# 05_LMS7002M_Misc.net
KiCad netlist of a schematic drawn in Altium Designer
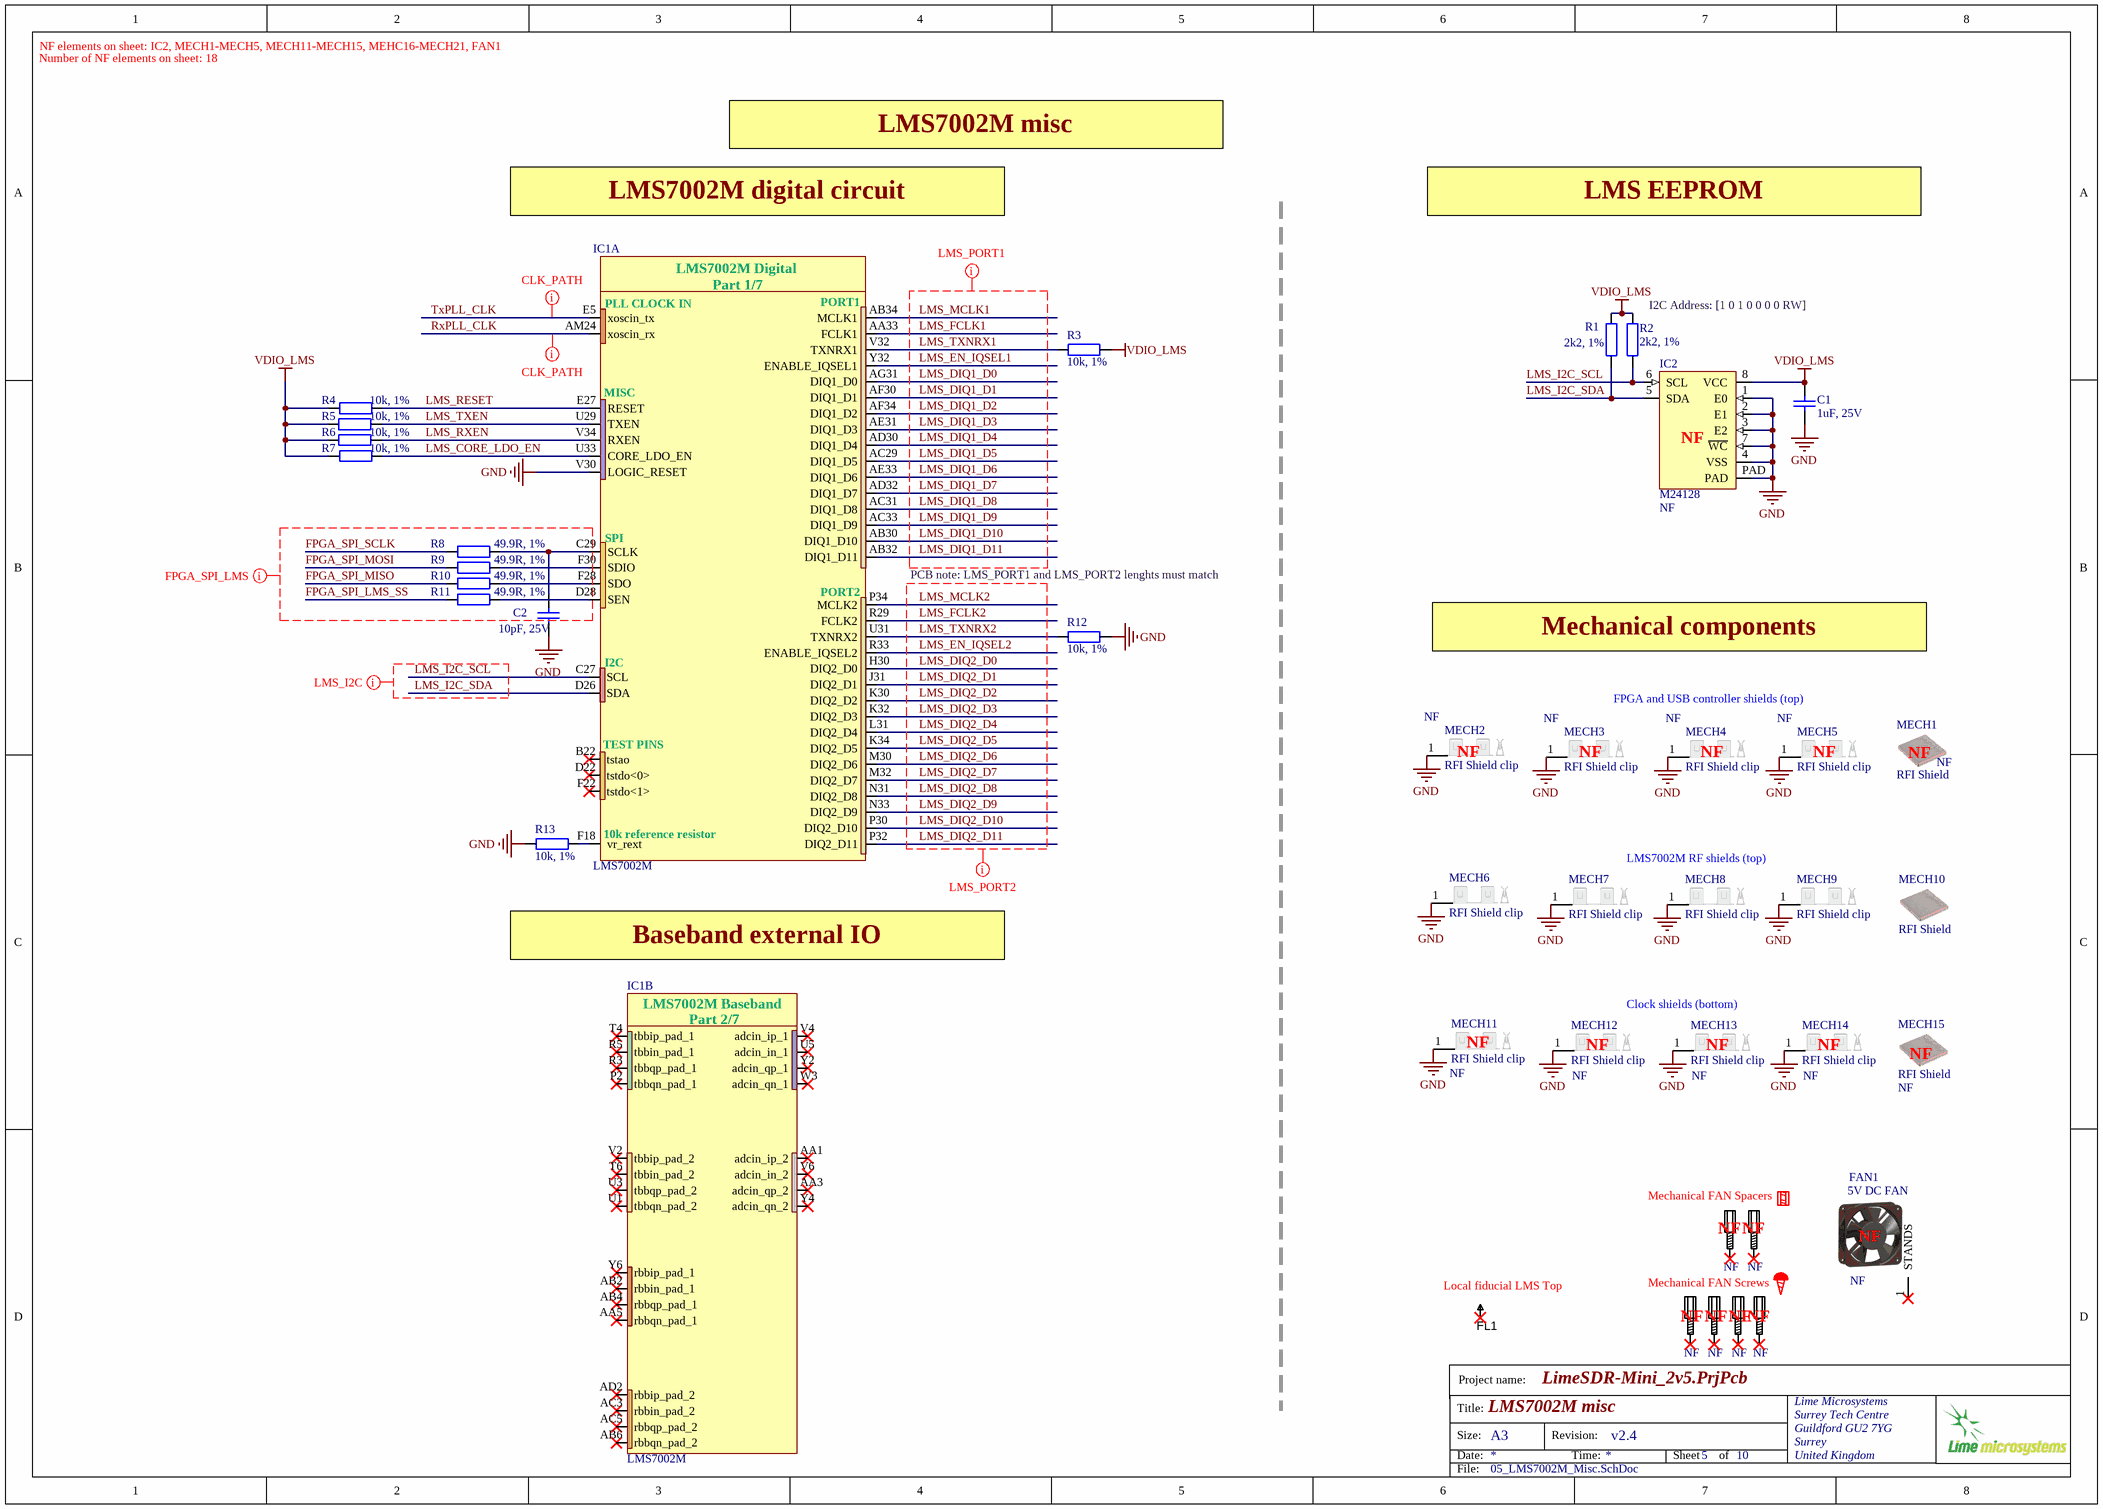
[diagram p0: 05_LMS7002M_Misc.SchDoc]

(export (version "E")
  (design (tool "Eeschema 10.0.6"))
  (components
    (comp (ref "C1")
      (value "1uF, 25V")
      (footprint "CAP0402")
      (fields (field (name "MANUFACTURER") "TDK"))
      (libsource (lib "LimeMicroAltiumLib_schLib") (part "Cap_0402"))
    )
    (comp (ref "C2")
      (value "10pF, 25V")
      (footprint "CAP0402")
      (fields (field (name "MANUFACTURER") "AVX"))
      (libsource (lib "LimeMicroAltiumLib_schLib") (part "Cap_0402"))
    )
    (comp (ref "FAN1")
      (value "5V DC FAN")
      (fields (field (name "MANUFACTURER") "Sunon Fans") (field (name "ASSEMBLY INFO") "NF"))
      (libsource (lib "LimeMicroAltiumLib_schLib") (part "12V_DC_FAN"))
    )
    (comp (ref "FL1")
      (value "Fiducial")
      (footprint "Fiducial_local")
      (libsource (lib "VGTU_Altium_lib") (part "Fiducial"))
    )
    (comp (ref "IC1")
      (value "LMS7002M")
      (footprint "LMS7002M_v5")
      (description "Schematic symbol revision 4. Default footprint - 0.31mm pad")
      (fields (field (name "MANUFACTURER") "Lime Microsystems"))
      (libsource (lib "LimeMicroAltiumLib_schLib_r04") (part "LMS7002Mr4"))
    )
    (comp (ref "IC2")
      (value "M24128")
      (footprint "M24128-DFMC6TG")
      (fields (field (name "MANUFACTURER") "STMicroelectronics") (field (name "ASSEMBLY INFO") "NF"))
      (libsource (lib "LimeMicroAltiumLib_schLib") (part "M24128-DFMC6TG"))
    )
    (comp (ref "MECH1")
      (value "RFI Shield")
      (footprint "WurthElectronic_RF_shield")
      (fields (field (name "MANUFACTURER") "WURTH ELEKTRONIK") (field (name "ASSEMBLY INFO") "NF"))
      (libsource (lib "LimeMicroAltiumLib_schLib") (part "RFI_SHIELD_1"))
    )
    (comp (ref "MECH2")
      (value "RFI Shield clip")
      (footprint "RFI_SHIELD_CLPS_MINI")
      (fields (field (name "MANUFACTURER") "HARWIN") (field (name "ASSEMBLY INFO") "NF"))
      (libsource (lib "LimeMicroAltiumLib_schLib") (part "RFI_SHIELD_CLIP"))
    )
    (comp (ref "MECH3")
      (value "RFI Shield clip")
      (footprint "RFI_SHIELD_CLPS_MINI")
      (fields (field (name "MANUFACTURER") "HARWIN") (field (name "ASSEMBLY INFO") "NF"))
      (libsource (lib "LimeMicroAltiumLib_schLib") (part "RFI_SHIELD_CLIP"))
    )
    (comp (ref "MECH4")
      (value "RFI Shield clip")
      (footprint "RFI_SHIELD_CLPS_MINI")
      (fields (field (name "MANUFACTURER") "HARWIN") (field (name "ASSEMBLY INFO") "NF"))
      (libsource (lib "LimeMicroAltiumLib_schLib") (part "RFI_SHIELD_CLIP"))
    )
    (comp (ref "MECH5")
      (value "RFI Shield clip")
      (footprint "RFI_SHIELD_CLPS_MINI")
      (fields (field (name "MANUFACTURER") "HARWIN") (field (name "ASSEMBLY INFO") "NF"))
      (libsource (lib "LimeMicroAltiumLib_schLib") (part "RFI_SHIELD_CLIP"))
    )
    (comp (ref "MECH6")
      (value "RFI Shield clip")
      (footprint "RFI_SHIELD_CLPS_MINI")
      (fields (field (name "MANUFACTURER") "HARWIN"))
      (libsource (lib "LimeMicroAltiumLib_schLib") (part "RFI_SHIELD_CLIP"))
    )
    (comp (ref "MECH7")
      (value "RFI Shield clip")
      (footprint "RFI_SHIELD_CLPS_MINI")
      (fields (field (name "MANUFACTURER") "HARWIN"))
      (libsource (lib "LimeMicroAltiumLib_schLib") (part "RFI_SHIELD_CLIP"))
    )
    (comp (ref "MECH8")
      (value "RFI Shield clip")
      (footprint "RFI_SHIELD_CLPS_MINI")
      (fields (field (name "MANUFACTURER") "HARWIN"))
      (libsource (lib "LimeMicroAltiumLib_schLib") (part "RFI_SHIELD_CLIP"))
    )
    (comp (ref "MECH9")
      (value "RFI Shield clip")
      (footprint "RFI_SHIELD_CLPS_MINI")
      (fields (field (name "MANUFACTURER") "HARWIN"))
      (libsource (lib "LimeMicroAltiumLib_schLib") (part "RFI_SHIELD_CLIP"))
    )
    (comp (ref "MECH10")
      (value "RFI Shield")
      (footprint "WurthElectronic_RF_shield")
      (fields (field (name "MANUFACTURER") "WURTH ELEKTRONIK"))
      (libsource (lib "LimeMicroAltiumLib_schLib") (part "RFI_SHIELD_1"))
    )
    (comp (ref "MECH11")
      (value "RFI Shield clip")
      (footprint "RFI_SHIELD_CLPS_MINI")
      (fields (field (name "MANUFACTURER") "HARWIN") (field (name "ASSEMBLY INFO") "NF"))
      (libsource (lib "LimeMicroAltiumLib_schLib") (part "RFI_SHIELD_CLIP"))
    )
    (comp (ref "MECH12")
      (value "RFI Shield clip")
      (footprint "RFI_SHIELD_CLPS_MINI")
      (fields (field (name "MANUFACTURER") "HARWIN") (field (name "ASSEMBLY INFO") "NF"))
      (libsource (lib "LimeMicroAltiumLib_schLib") (part "RFI_SHIELD_CLIP"))
    )
    (comp (ref "MECH13")
      (value "RFI Shield clip")
      (footprint "RFI_SHIELD_CLPS_MINI")
      (fields (field (name "MANUFACTURER") "HARWIN") (field (name "ASSEMBLY INFO") "NF"))
      (libsource (lib "LimeMicroAltiumLib_schLib") (part "RFI_SHIELD_CLIP"))
    )
    (comp (ref "MECH14")
      (value "RFI Shield clip")
      (footprint "RFI_SHIELD_CLPS_MINI")
      (fields (field (name "MANUFACTURER") "HARWIN") (field (name "ASSEMBLY INFO") "NF"))
      (libsource (lib "LimeMicroAltiumLib_schLib") (part "RFI_SHIELD_CLIP"))
    )
    (comp (ref "MECH15")
      (value "RFI Shield")
      (footprint "WurthElectronic_RF_shield")
      (fields (field (name "MANUFACTURER") "WURTH ELEKTRONIK") (field (name "ASSEMBLY INFO") "NF"))
      (libsource (lib "LimeMicroAltiumLib_schLib") (part "RFI_SHIELD_1"))
    )
    (comp (ref "MECH16")
      (value "Spacer M3")
      (description "STANDOFF M/F MET 5MM HEX 10MM L")
      (fields (field (name "MANUFACTURER") "BOSSARD") (field (name "ASSEMBLY INFO") "NF"))
      (libsource (lib "LimeMicroAltiumLib_schLib") (part "STANDOFF_M-F_THREADED_M3x8x10mm_HEX_5mm dia"))
    )
    (comp (ref "MECH17")
      (value "Spacer M3")
      (description "STANDOFF M/F MET 5MM HEX 10MM L")
      (fields (field (name "MANUFACTURER") "BOSSARD") (field (name "ASSEMBLY INFO") "NF"))
      (libsource (lib "LimeMicroAltiumLib_schLib") (part "STANDOFF_M-F_THREADED_M3x8x10mm_HEX_5mm dia"))
    )
    (comp (ref "MECH18")
      (value "Screws M3 v1")
      (description "STANDOFF M/F MET 5MM HEX 10MM L")
      (fields (field (name "MANUFACTURER") "KRAFTBERG") (field (name "ASSEMBLY INFO") "NF"))
      (libsource (lib "LimeMicroAltiumLib_schLib") (part "STANDOFF_M-F_THREADED_M3x8x10mm_HEX_5mm dia"))
    )
    (comp (ref "MECH19")
      (value "Screws M3 v1")
      (description "STANDOFF M/F MET 5MM HEX 10MM L")
      (fields (field (name "MANUFACTURER") "KRAFTBERG") (field (name "ASSEMBLY INFO") "NF"))
      (libsource (lib "LimeMicroAltiumLib_schLib") (part "STANDOFF_M-F_THREADED_M3x8x10mm_HEX_5mm dia"))
    )
    (comp (ref "MECH20")
      (value "Screws M3 v2")
      (description "STANDOFF M/F MET 5MM HEX 10MM L")
      (fields (field (name "MANUFACTURER") "KRAFTBERG") (field (name "ASSEMBLY INFO") "NF"))
      (libsource (lib "LimeMicroAltiumLib_schLib") (part "STANDOFF_M-F_THREADED_M3x8x10mm_HEX_5mm dia"))
    )
    (comp (ref "MECH21")
      (value "Screws M3 v2")
      (description "STANDOFF M/F MET 5MM HEX 10MM L")
      (fields (field (name "MANUFACTURER") "KRAFTBERG") (field (name "ASSEMBLY INFO") "NF"))
      (libsource (lib "LimeMicroAltiumLib_schLib") (part "STANDOFF_M-F_THREADED_M3x8x10mm_HEX_5mm dia"))
    )
    (comp (ref "R1")
      (value "2k2, 1%")
      (footprint "RES0402")
      (fields (field (name "MANUFACTURER") "Stackpole Electronics Inc") (field (name "TOLERANCE") "±1%"))
      (libsource (lib "LimeMicroAltiumLib_schLib") (part "Res_0402"))
    )
    (comp (ref "R2")
      (value "2k2, 1%")
      (footprint "RES0402")
      (fields (field (name "MANUFACTURER") "Stackpole Electronics Inc") (field (name "TOLERANCE") "±1%"))
      (libsource (lib "LimeMicroAltiumLib_schLib") (part "Res_0402"))
    )
    (comp (ref "R3")
      (value "10k, 1%")
      (footprint "RES0402")
      (fields (field (name "MANUFACTURER") "Yageo") (field (name "TOLERANCE") "±1%"))
      (libsource (lib "LimeMicroAltiumLib_schLib") (part "Res_0402"))
    )
    (comp (ref "R4")
      (value "10k, 1%")
      (footprint "RES0402")
      (fields (field (name "MANUFACTURER") "Yageo") (field (name "TOLERANCE") "±1%"))
      (libsource (lib "LimeMicroAltiumLib_schLib") (part "Res_0402"))
    )
    (comp (ref "R5")
      (value "10k, 1%")
      (footprint "RES0402")
      (fields (field (name "MANUFACTURER") "Yageo") (field (name "TOLERANCE") "±1%"))
      (libsource (lib "LimeMicroAltiumLib_schLib") (part "Res_0402"))
    )
    (comp (ref "R6")
      (value "10k, 1%")
      (footprint "RES0402")
      (fields (field (name "MANUFACTURER") "Yageo") (field (name "TOLERANCE") "±1%"))
      (libsource (lib "LimeMicroAltiumLib_schLib") (part "Res_0402"))
    )
    (comp (ref "R7")
      (value "10k, 1%")
      (footprint "RES0402")
      (fields (field (name "MANUFACTURER") "Yageo") (field (name "TOLERANCE") "±1%"))
      (libsource (lib "LimeMicroAltiumLib_schLib") (part "Res_0402"))
    )
    (comp (ref "R8")
      (value "49.9R, 1%")
      (footprint "RES0402")
      (fields
        (field (name "TOLERANCE") "±1%")
        (field (name "MANUFACTURER") "Samsung Electro-Mechanics America, Inc.")
      )
      (libsource (lib "LimeMicroAltiumLib_schLib") (part "Res_0402"))
    )
    (comp (ref "R9")
      (value "49.9R, 1%")
      (footprint "RES0402")
      (fields
        (field (name "TOLERANCE") "±1%")
        (field (name "MANUFACTURER") "Samsung Electro-Mechanics America, Inc.")
      )
      (libsource (lib "LimeMicroAltiumLib_schLib") (part "Res_0402"))
    )
    (comp (ref "R10")
      (value "49.9R, 1%")
      (footprint "RES0402")
      (fields
        (field (name "TOLERANCE") "±1%")
        (field (name "MANUFACTURER") "Samsung Electro-Mechanics America, Inc.")
      )
      (libsource (lib "LimeMicroAltiumLib_schLib") (part "Res_0402"))
    )
    (comp (ref "R11")
      (value "49.9R, 1%")
      (footprint "RES0402")
      (fields
        (field (name "TOLERANCE") "±1%")
        (field (name "MANUFACTURER") "Samsung Electro-Mechanics America, Inc.")
      )
      (libsource (lib "LimeMicroAltiumLib_schLib") (part "Res_0402"))
    )
    (comp (ref "R12")
      (value "10k, 1%")
      (footprint "RES0402")
      (fields (field (name "MANUFACTURER") "Yageo") (field (name "TOLERANCE") "±1%"))
      (libsource (lib "LimeMicroAltiumLib_schLib") (part "Res_0402"))
    )
    (comp (ref "R13")
      (value "10k, 1%")
      (footprint "RES0402")
      (fields (field (name "MANUFACTURER") "Yageo") (field (name "TOLERANCE") "±1%"))
      (libsource (lib "LimeMicroAltiumLib_schLib") (part "Res_0402"))
    )
  )
  (nets
    (net (code "1") (name "/FPGA_SPI_LMS_SS") (class "Default")
      (node (ref "R11") (pin "2") (pinfunction "2_2") (pintype "passive"))
    )
    (net (code "2") (name "/FPGA_SPI_MISO") (class "Default")
      (node (ref "R10") (pin "2") (pinfunction "2_2") (pintype "passive"))
    )
    (net (code "3") (name "/FPGA_SPI_MOSI") (class "Default")
      (node (ref "R9") (pin "2") (pinfunction "2_2") (pintype "passive"))
    )
    (net (code "4") (name "/FPGA_SPI_SCLK") (class "Default")
      (node (ref "R8") (pin "2") (pinfunction "2_2") (pintype "passive"))
    )
    (net (code "5") (name "/LMS_CORE_LDO_EN") (class "Default")
      (node (ref "IC1") (pin "U33") (pinfunction "CORE_LDO_EN_U33") (pintype "passive"))
      (node (ref "R7") (pin "1") (pinfunction "1_1") (pintype "passive"))
    )
    (net (code "6") (name "/LMS_DIQ1_D0") (class "Default")
      (node (ref "IC1") (pin "AG31") (pinfunction "DIQ1_D0_AG31") (pintype "passive"))
    )
    (net (code "7") (name "/LMS_DIQ1_D1") (class "Default")
      (node (ref "IC1") (pin "AF30") (pinfunction "DIQ1_D1_AF30") (pintype "passive"))
    )
    (net (code "8") (name "/LMS_DIQ1_D2") (class "Default")
      (node (ref "IC1") (pin "AF34") (pinfunction "DIQ1_D2_AF34") (pintype "passive"))
    )
    (net (code "9") (name "/LMS_DIQ1_D3") (class "Default")
      (node (ref "IC1") (pin "AE31") (pinfunction "DIQ1_D3_AE31") (pintype "passive"))
    )
    (net (code "10") (name "/LMS_DIQ1_D4") (class "Default")
      (node (ref "IC1") (pin "AD30") (pinfunction "DIQ1_D4_AD30") (pintype "passive"))
    )
    (net (code "11") (name "/LMS_DIQ1_D5") (class "Default")
      (node (ref "IC1") (pin "AC29") (pinfunction "DIQ1_D5_AC29") (pintype "passive"))
    )
    (net (code "12") (name "/LMS_DIQ1_D6") (class "Default")
      (node (ref "IC1") (pin "AE33") (pinfunction "DIQ1_D6_AE33") (pintype "passive"))
    )
    (net (code "13") (name "/LMS_DIQ1_D7") (class "Default")
      (node (ref "IC1") (pin "AD32") (pinfunction "DIQ1_D7_AD32") (pintype "passive"))
    )
    (net (code "14") (name "/LMS_DIQ1_D8") (class "Default")
      (node (ref "IC1") (pin "AC31") (pinfunction "DIQ1_D8_AC31") (pintype "passive"))
    )
    (net (code "15") (name "/LMS_DIQ1_D9") (class "Default")
      (node (ref "IC1") (pin "AC33") (pinfunction "DIQ1_D9_AC33") (pintype "passive"))
    )
    (net (code "16") (name "/LMS_DIQ1_D10") (class "Default")
      (node (ref "IC1") (pin "AB30") (pinfunction "DIQ1_D10_AB30") (pintype "passive"))
    )
    (net (code "17") (name "/LMS_DIQ1_D11") (class "Default")
      (node (ref "IC1") (pin "AB32") (pinfunction "DIQ1_D11_AB32") (pintype "passive"))
    )
    (net (code "18") (name "/LMS_DIQ2_D0") (class "Default")
      (node (ref "IC1") (pin "H30") (pinfunction "DIQ2_D0_H30") (pintype "passive"))
    )
    (net (code "19") (name "/LMS_DIQ2_D1") (class "Default")
      (node (ref "IC1") (pin "J31") (pinfunction "DIQ2_D1_J31") (pintype "passive"))
    )
    (net (code "20") (name "/LMS_DIQ2_D2") (class "Default")
      (node (ref "IC1") (pin "K30") (pinfunction "DIQ2_D2_K30") (pintype "passive"))
    )
    (net (code "21") (name "/LMS_DIQ2_D3") (class "Default")
      (node (ref "IC1") (pin "K32") (pinfunction "DIQ2_D3_K32") (pintype "passive"))
    )
    (net (code "22") (name "/LMS_DIQ2_D4") (class "Default")
      (node (ref "IC1") (pin "L31") (pinfunction "DIQ2_D4_L31") (pintype "passive"))
    )
    (net (code "23") (name "/LMS_DIQ2_D5") (class "Default")
      (node (ref "IC1") (pin "K34") (pinfunction "DIQ2_D5_K34") (pintype "passive"))
    )
    (net (code "24") (name "/LMS_DIQ2_D6") (class "Default")
      (node (ref "IC1") (pin "M30") (pinfunction "DIQ2_D6_M30") (pintype "passive"))
    )
    (net (code "25") (name "/LMS_DIQ2_D7") (class "Default")
      (node (ref "IC1") (pin "M32") (pinfunction "DIQ2_D7_M32") (pintype "passive"))
    )
    (net (code "26") (name "/LMS_DIQ2_D8") (class "Default")
      (node (ref "IC1") (pin "N31") (pinfunction "DIQ2_D8_N31") (pintype "passive"))
    )
    (net (code "27") (name "/LMS_DIQ2_D9") (class "Default")
      (node (ref "IC1") (pin "N33") (pinfunction "DIQ2_D9_N33") (pintype "passive"))
    )
    (net (code "28") (name "/LMS_DIQ2_D10") (class "Default")
      (node (ref "IC1") (pin "P30") (pinfunction "DIQ2_D10_P30") (pintype "passive"))
    )
    (net (code "29") (name "/LMS_DIQ2_D11") (class "Default")
      (node (ref "IC1") (pin "P32") (pinfunction "DIQ2_D11_P32") (pintype "passive"))
    )
    (net (code "30") (name "/LMS_EN_IQSEL1") (class "Default")
      (node (ref "IC1") (pin "Y32") (pinfunction "ENABLE_IQSEL1_Y32") (pintype "passive"))
    )
    (net (code "31") (name "/LMS_EN_IQSEL2") (class "Default")
      (node (ref "IC1") (pin "R33") (pinfunction "ENABLE_IQSEL2_R33") (pintype "passive"))
    )
    (net (code "32") (name "/LMS_FCLK1") (class "Default")
      (node (ref "IC1") (pin "AA33") (pinfunction "FCLK1_AA33") (pintype "passive"))
    )
    (net (code "33") (name "/LMS_FCLK2") (class "Default")
      (node (ref "IC1") (pin "R29") (pinfunction "FCLK2_R29") (pintype "passive"))
    )
    (net (code "34") (name "/LMS_I2C_SCL") (class "Default")
      (node (ref "IC1") (pin "C27") (pinfunction "SCL_C27") (pintype "passive"))
      (node (ref "IC2") (pin "6") (pinfunction "SCL_6") (pintype "input"))
      (node (ref "R2") (pin "2") (pinfunction "2_2") (pintype "passive"))
    )
    (net (code "35") (name "/LMS_I2C_SDA") (class "Default")
      (node (ref "IC1") (pin "D26") (pinfunction "SDA_D26") (pintype "passive"))
      (node (ref "IC2") (pin "5") (pinfunction "SDA_5") (pintype "bidirectional"))
      (node (ref "R1") (pin "2") (pinfunction "2_2") (pintype "passive"))
    )
    (net (code "36") (name "/LMS_MCLK1") (class "Default")
      (node (ref "IC1") (pin "AB34") (pinfunction "MCLK1_AB34") (pintype "passive"))
    )
    (net (code "37") (name "/LMS_MCLK2") (class "Default")
      (node (ref "IC1") (pin "P34") (pinfunction "MCLK2_P34") (pintype "passive"))
    )
    (net (code "38") (name "/LMS_RESET") (class "Default")
      (node (ref "IC1") (pin "E27") (pinfunction "RESET_E27") (pintype "passive"))
      (node (ref "R4") (pin "1") (pinfunction "1_1") (pintype "passive"))
    )
    (net (code "39") (name "/LMS_RXEN") (class "Default")
      (node (ref "IC1") (pin "V34") (pinfunction "RXEN_V34") (pintype "passive"))
      (node (ref "R6") (pin "2") (pinfunction "2_2") (pintype "passive"))
    )
    (net (code "40") (name "/LMS_TXEN") (class "Default")
      (node (ref "IC1") (pin "U29") (pinfunction "TXEN_U29") (pintype "passive"))
      (node (ref "R5") (pin "2") (pinfunction "2_2") (pintype "passive"))
    )
    (net (code "41") (name "/LMS_TXNRX1") (class "Default")
      (node (ref "IC1") (pin "V32") (pinfunction "TXNRX1_V32") (pintype "passive"))
      (node (ref "R3") (pin "1") (pinfunction "1_1") (pintype "passive"))
    )
    (net (code "42") (name "/LMS_TXNRX2") (class "Default")
      (node (ref "IC1") (pin "U31") (pinfunction "TXNRX2_U31") (pintype "passive"))
      (node (ref "R12") (pin "1") (pinfunction "1_1") (pintype "passive"))
    )
    (net (code "43") (name "/RxPLL_CLK") (class "Default")
      (node (ref "IC1") (pin "AM24") (pinfunction "xoscin_rx_AM24") (pintype "passive"))
    )
    (net (code "44") (name "/TxPLL_CLK") (class "Default")
      (node (ref "IC1") (pin "E5") (pinfunction "xoscin_tx_E5") (pintype "passive"))
    )
    (net (code "45") (name "GND") (class "Default")
      (node (ref "C1") (pin "2") (pinfunction "2_2") (pintype "passive"))
      (node (ref "C2") (pin "2") (pinfunction "2_2") (pintype "passive"))
      (node (ref "IC1") (pin "V30") (pinfunction "LOGIC_RESET_V30") (pintype "passive"))
      (node (ref "IC2") (pin "1") (pinfunction "E0_1") (pintype "input"))
      (node (ref "IC2") (pin "2") (pinfunction "E1_2") (pintype "input"))
      (node (ref "IC2") (pin "3") (pinfunction "E2_3") (pintype "input"))
      (node (ref "IC2") (pin "4") (pinfunction "VSS_4") (pintype "power_in"))
      (node (ref "IC2") (pin "7") (pinfunction "~{WC}_7") (pintype "input"))
      (node (ref "IC2") (pin "PAD") (pinfunction "PAD_PAD") (pintype "power_in"))
      (node (ref "MECH11") (pin "1") (pinfunction "GND_1") (pintype "passive"))
      (node (ref "MECH12") (pin "1") (pinfunction "GND_1") (pintype "passive"))
      (node (ref "MECH13") (pin "1") (pinfunction "GND_1") (pintype "passive"))
      (node (ref "MECH14") (pin "1") (pinfunction "GND_1") (pintype "passive"))
      (node (ref "MECH2") (pin "1") (pinfunction "GND_1") (pintype "passive"))
      (node (ref "MECH3") (pin "1") (pinfunction "GND_1") (pintype "passive"))
      (node (ref "MECH4") (pin "1") (pinfunction "GND_1") (pintype "passive"))
      (node (ref "MECH5") (pin "1") (pinfunction "GND_1") (pintype "passive"))
      (node (ref "MECH6") (pin "1") (pinfunction "GND_1") (pintype "passive"))
      (node (ref "MECH7") (pin "1") (pinfunction "GND_1") (pintype "passive"))
      (node (ref "MECH8") (pin "1") (pinfunction "GND_1") (pintype "passive"))
      (node (ref "MECH9") (pin "1") (pinfunction "GND_1") (pintype "passive"))
      (node (ref "R12") (pin "2") (pinfunction "2_2") (pintype "passive"))
      (node (ref "R13") (pin "2") (pinfunction "2_2") (pintype "passive"))
    )
    (net (code "46") (name "Net-(IC1A-SCLK)") (class "Default")
      (node (ref "C2") (pin "1") (pinfunction "1_1") (pintype "passive"))
      (node (ref "IC1") (pin "C29") (pinfunction "SCLK_C29") (pintype "passive"))
      (node (ref "R8") (pin "1") (pinfunction "1_1") (pintype "passive"))
    )
    (net (code "47") (name "Net-(IC1A-SDIO)") (class "Default")
      (node (ref "IC1") (pin "F30") (pinfunction "SDIO_F30") (pintype "passive"))
      (node (ref "R9") (pin "1") (pinfunction "1_1") (pintype "passive"))
    )
    (net (code "48") (name "Net-(IC1A-SDO)") (class "Default")
      (node (ref "IC1") (pin "F28") (pinfunction "SDO_F28") (pintype "passive"))
      (node (ref "R10") (pin "1") (pinfunction "1_1") (pintype "passive"))
    )
    (net (code "49") (name "Net-(IC1A-SEN)") (class "Default")
      (node (ref "IC1") (pin "D28") (pinfunction "SEN_D28") (pintype "passive"))
      (node (ref "R11") (pin "1") (pinfunction "1_1") (pintype "passive"))
    )
    (net (code "50") (name "Net-(IC1A-vr_rext)") (class "Default")
      (node (ref "IC1") (pin "F18") (pinfunction "vr_rext_F18") (pintype "passive"))
      (node (ref "R13") (pin "1") (pinfunction "1_1") (pintype "passive"))
    )
    (net (code "51") (name "VDIO_LMS") (class "Default")
      (node (ref "C1") (pin "1") (pinfunction "1_1") (pintype "passive"))
      (node (ref "IC2") (pin "8") (pinfunction "VCC_8") (pintype "power_in"))
      (node (ref "R1") (pin "1") (pinfunction "1_1") (pintype "passive"))
      (node (ref "R2") (pin "1") (pinfunction "1_1") (pintype "passive"))
      (node (ref "R3") (pin "2") (pinfunction "2_2") (pintype "passive"))
      (node (ref "R4") (pin "2") (pinfunction "2_2") (pintype "passive"))
      (node (ref "R5") (pin "1") (pinfunction "1_1") (pintype "passive"))
      (node (ref "R6") (pin "1") (pinfunction "1_1") (pintype "passive"))
      (node (ref "R7") (pin "2") (pinfunction "2_2") (pintype "passive"))
    )
    (net (code "52") (name "unconnected-(FAN1-STANDS-Pad1)") (class "Default")
      (node (ref "FAN1") (pin "1") (pinfunction "STANDS_1") (pintype "passive+no_connect"))
    )
    (net (code "53") (name "unconnected-(FL1-Pad1)") (class "Default")
      (node (ref "FL1") (pin "1") (pintype "passive+no_connect"))
    )
    (net (code "54") (name "unconnected-(IC1A-tstao-PadB22)") (class "Default")
      (node (ref "IC1") (pin "B22") (pinfunction "tstao_B22") (pintype "passive+no_connect"))
    )
    (net (code "55") (name "unconnected-(IC1A-tstdo<0>-PadD22)") (class "Default")
      (node (ref "IC1") (pin "D22") (pinfunction "tstdo<0>_D22") (pintype "passive+no_connect"))
    )
    (net (code "56") (name "unconnected-(IC1A-tstdo<1>-PadF22)") (class "Default")
      (node (ref "IC1") (pin "F22") (pinfunction "tstdo<1>_F22") (pintype "passive+no_connect"))
    )
    (net (code "57") (name "unconnected-(IC1B-adcin_in_1-PadU5)") (class "Default")
      (node (ref "IC1") (pin "U5") (pinfunction "adcin_in_1_U5") (pintype "passive+no_connect"))
    )
    (net (code "58") (name "unconnected-(IC1B-adcin_in_2-PadV6)") (class "Default")
      (node (ref "IC1") (pin "V6") (pinfunction "adcin_in_2_V6") (pintype "passive+no_connect"))
    )
    (net (code "59") (name "unconnected-(IC1B-adcin_ip_1-PadV4)") (class "Default")
      (node (ref "IC1") (pin "V4") (pinfunction "adcin_ip_1_V4") (pintype "passive+no_connect"))
    )
    (net (code "60") (name "unconnected-(IC1B-adcin_ip_2-PadAA1)") (class "Default")
      (node (ref "IC1") (pin "AA1") (pinfunction "adcin_ip_2_AA1") (pintype "passive+no_connect"))
    )
    (net (code "61") (name "unconnected-(IC1B-adcin_qn_1-PadW3)") (class "Default")
      (node (ref "IC1") (pin "W3") (pinfunction "adcin_qn_1_W3") (pintype "passive+no_connect"))
    )
    (net (code "62") (name "unconnected-(IC1B-adcin_qn_2-PadY4)") (class "Default")
      (node (ref "IC1") (pin "Y4") (pinfunction "adcin_qn_2_Y4") (pintype "passive+no_connect"))
    )
    (net (code "63") (name "unconnected-(IC1B-adcin_qp_1-PadY2)") (class "Default")
      (node (ref "IC1") (pin "Y2") (pinfunction "adcin_qp_1_Y2") (pintype "passive+no_connect"))
    )
    (net (code "64") (name "unconnected-(IC1B-adcin_qp_2-PadAA3)") (class "Default")
      (node (ref "IC1") (pin "AA3") (pinfunction "adcin_qp_2_AA3") (pintype "passive+no_connect"))
    )
    (net (code "65") (name "unconnected-(IC1B-rbbin_pad_1-PadAB2)") (class "Default")
      (node (ref "IC1") (pin "AB2") (pinfunction "rbbin_pad_1_AB2") (pintype "passive+no_connect"))
    )
    (net (code "66") (name "unconnected-(IC1B-rbbin_pad_2-PadAC3)") (class "Default")
      (node (ref "IC1") (pin "AC3") (pinfunction "rbbin_pad_2_AC3") (pintype "passive+no_connect"))
    )
    (net (code "67") (name "unconnected-(IC1B-rbbip_pad_1-PadY6)") (class "Default")
      (node (ref "IC1") (pin "Y6") (pinfunction "rbbip_pad_1_Y6") (pintype "passive+no_connect"))
    )
    (net (code "68") (name "unconnected-(IC1B-rbbip_pad_2-PadAD2)") (class "Default")
      (node (ref "IC1") (pin "AD2") (pinfunction "rbbip_pad_2_AD2") (pintype "passive+no_connect"))
    )
    (net (code "69") (name "unconnected-(IC1B-rbbqn_pad_1-PadAA5)") (class "Default")
      (node (ref "IC1") (pin "AA5") (pinfunction "rbbqn_pad_1_AA5") (pintype "passive+no_connect"))
    )
    (net (code "70") (name "unconnected-(IC1B-rbbqn_pad_2-PadAB6)") (class "Default")
      (node (ref "IC1") (pin "AB6") (pinfunction "rbbqn_pad_2_AB6") (pintype "passive+no_connect"))
    )
    (net (code "71") (name "unconnected-(IC1B-rbbqp_pad_1-PadAB4)") (class "Default")
      (node (ref "IC1") (pin "AB4") (pinfunction "rbbqp_pad_1_AB4") (pintype "passive+no_connect"))
    )
    (net (code "72") (name "unconnected-(IC1B-rbbqp_pad_2-PadAC5)") (class "Default")
      (node (ref "IC1") (pin "AC5") (pinfunction "rbbqp_pad_2_AC5") (pintype "passive+no_connect"))
    )
    (net (code "73") (name "unconnected-(IC1B-tbbin_pad_1-PadR5)") (class "Default")
      (node (ref "IC1") (pin "R5") (pinfunction "tbbin_pad_1_R5") (pintype "passive+no_connect"))
    )
    (net (code "74") (name "unconnected-(IC1B-tbbin_pad_2-PadT6)") (class "Default")
      (node (ref "IC1") (pin "T6") (pinfunction "tbbin_pad_2_T6") (pintype "passive+no_connect"))
    )
    (net (code "75") (name "unconnected-(IC1B-tbbip_pad_1-PadT4)") (class "Default")
      (node (ref "IC1") (pin "T4") (pinfunction "tbbip_pad_1_T4") (pintype "passive+no_connect"))
    )
    (net (code "76") (name "unconnected-(IC1B-tbbip_pad_2-PadV2)") (class "Default")
      (node (ref "IC1") (pin "V2") (pinfunction "tbbip_pad_2_V2") (pintype "passive+no_connect"))
    )
    (net (code "77") (name "unconnected-(IC1B-tbbqn_pad_1-PadP2)") (class "Default")
      (node (ref "IC1") (pin "P2") (pinfunction "tbbqn_pad_1_P2") (pintype "passive+no_connect"))
    )
    (net (code "78") (name "unconnected-(IC1B-tbbqn_pad_2-PadU1)") (class "Default")
      (node (ref "IC1") (pin "U1") (pinfunction "tbbqn_pad_2_U1") (pintype "passive+no_connect"))
    )
    (net (code "79") (name "unconnected-(IC1B-tbbqp_pad_1-PadR3)") (class "Default")
      (node (ref "IC1") (pin "R3") (pinfunction "tbbqp_pad_1_R3") (pintype "passive+no_connect"))
    )
    (net (code "80") (name "unconnected-(IC1B-tbbqp_pad_2-PadU3)") (class "Default")
      (node (ref "IC1") (pin "U3") (pinfunction "tbbqp_pad_2_U3") (pintype "passive+no_connect"))
    )
    (net (code "81") (name "unconnected-(MECH16-PadMH1)") (class "Default")
      (node (ref "MECH16") (pin "MH1") (pinfunction "MH1_MH1") (pintype "passive+no_connect"))
    )
    (net (code "82") (name "unconnected-(MECH17-PadMH1)") (class "Default")
      (node (ref "MECH17") (pin "MH1") (pinfunction "MH1_MH1") (pintype "passive+no_connect"))
    )
    (net (code "83") (name "unconnected-(MECH18-PadMH1)") (class "Default")
      (node (ref "MECH18") (pin "MH1") (pinfunction "MH1_MH1") (pintype "passive+no_connect"))
    )
    (net (code "84") (name "unconnected-(MECH19-PadMH1)") (class "Default")
      (node (ref "MECH19") (pin "MH1") (pinfunction "MH1_MH1") (pintype "passive+no_connect"))
    )
    (net (code "85") (name "unconnected-(MECH20-PadMH1)") (class "Default")
      (node (ref "MECH20") (pin "MH1") (pinfunction "MH1_MH1") (pintype "passive+no_connect"))
    )
    (net (code "86") (name "unconnected-(MECH21-PadMH1)") (class "Default")
      (node (ref "MECH21") (pin "MH1") (pinfunction "MH1_MH1") (pintype "passive+no_connect"))
    )
  )
)
